# sch_claudia-2_0-the-real-thing_2026-05-1.net
KiCad netlist of a schematic drawn in EasyEDA
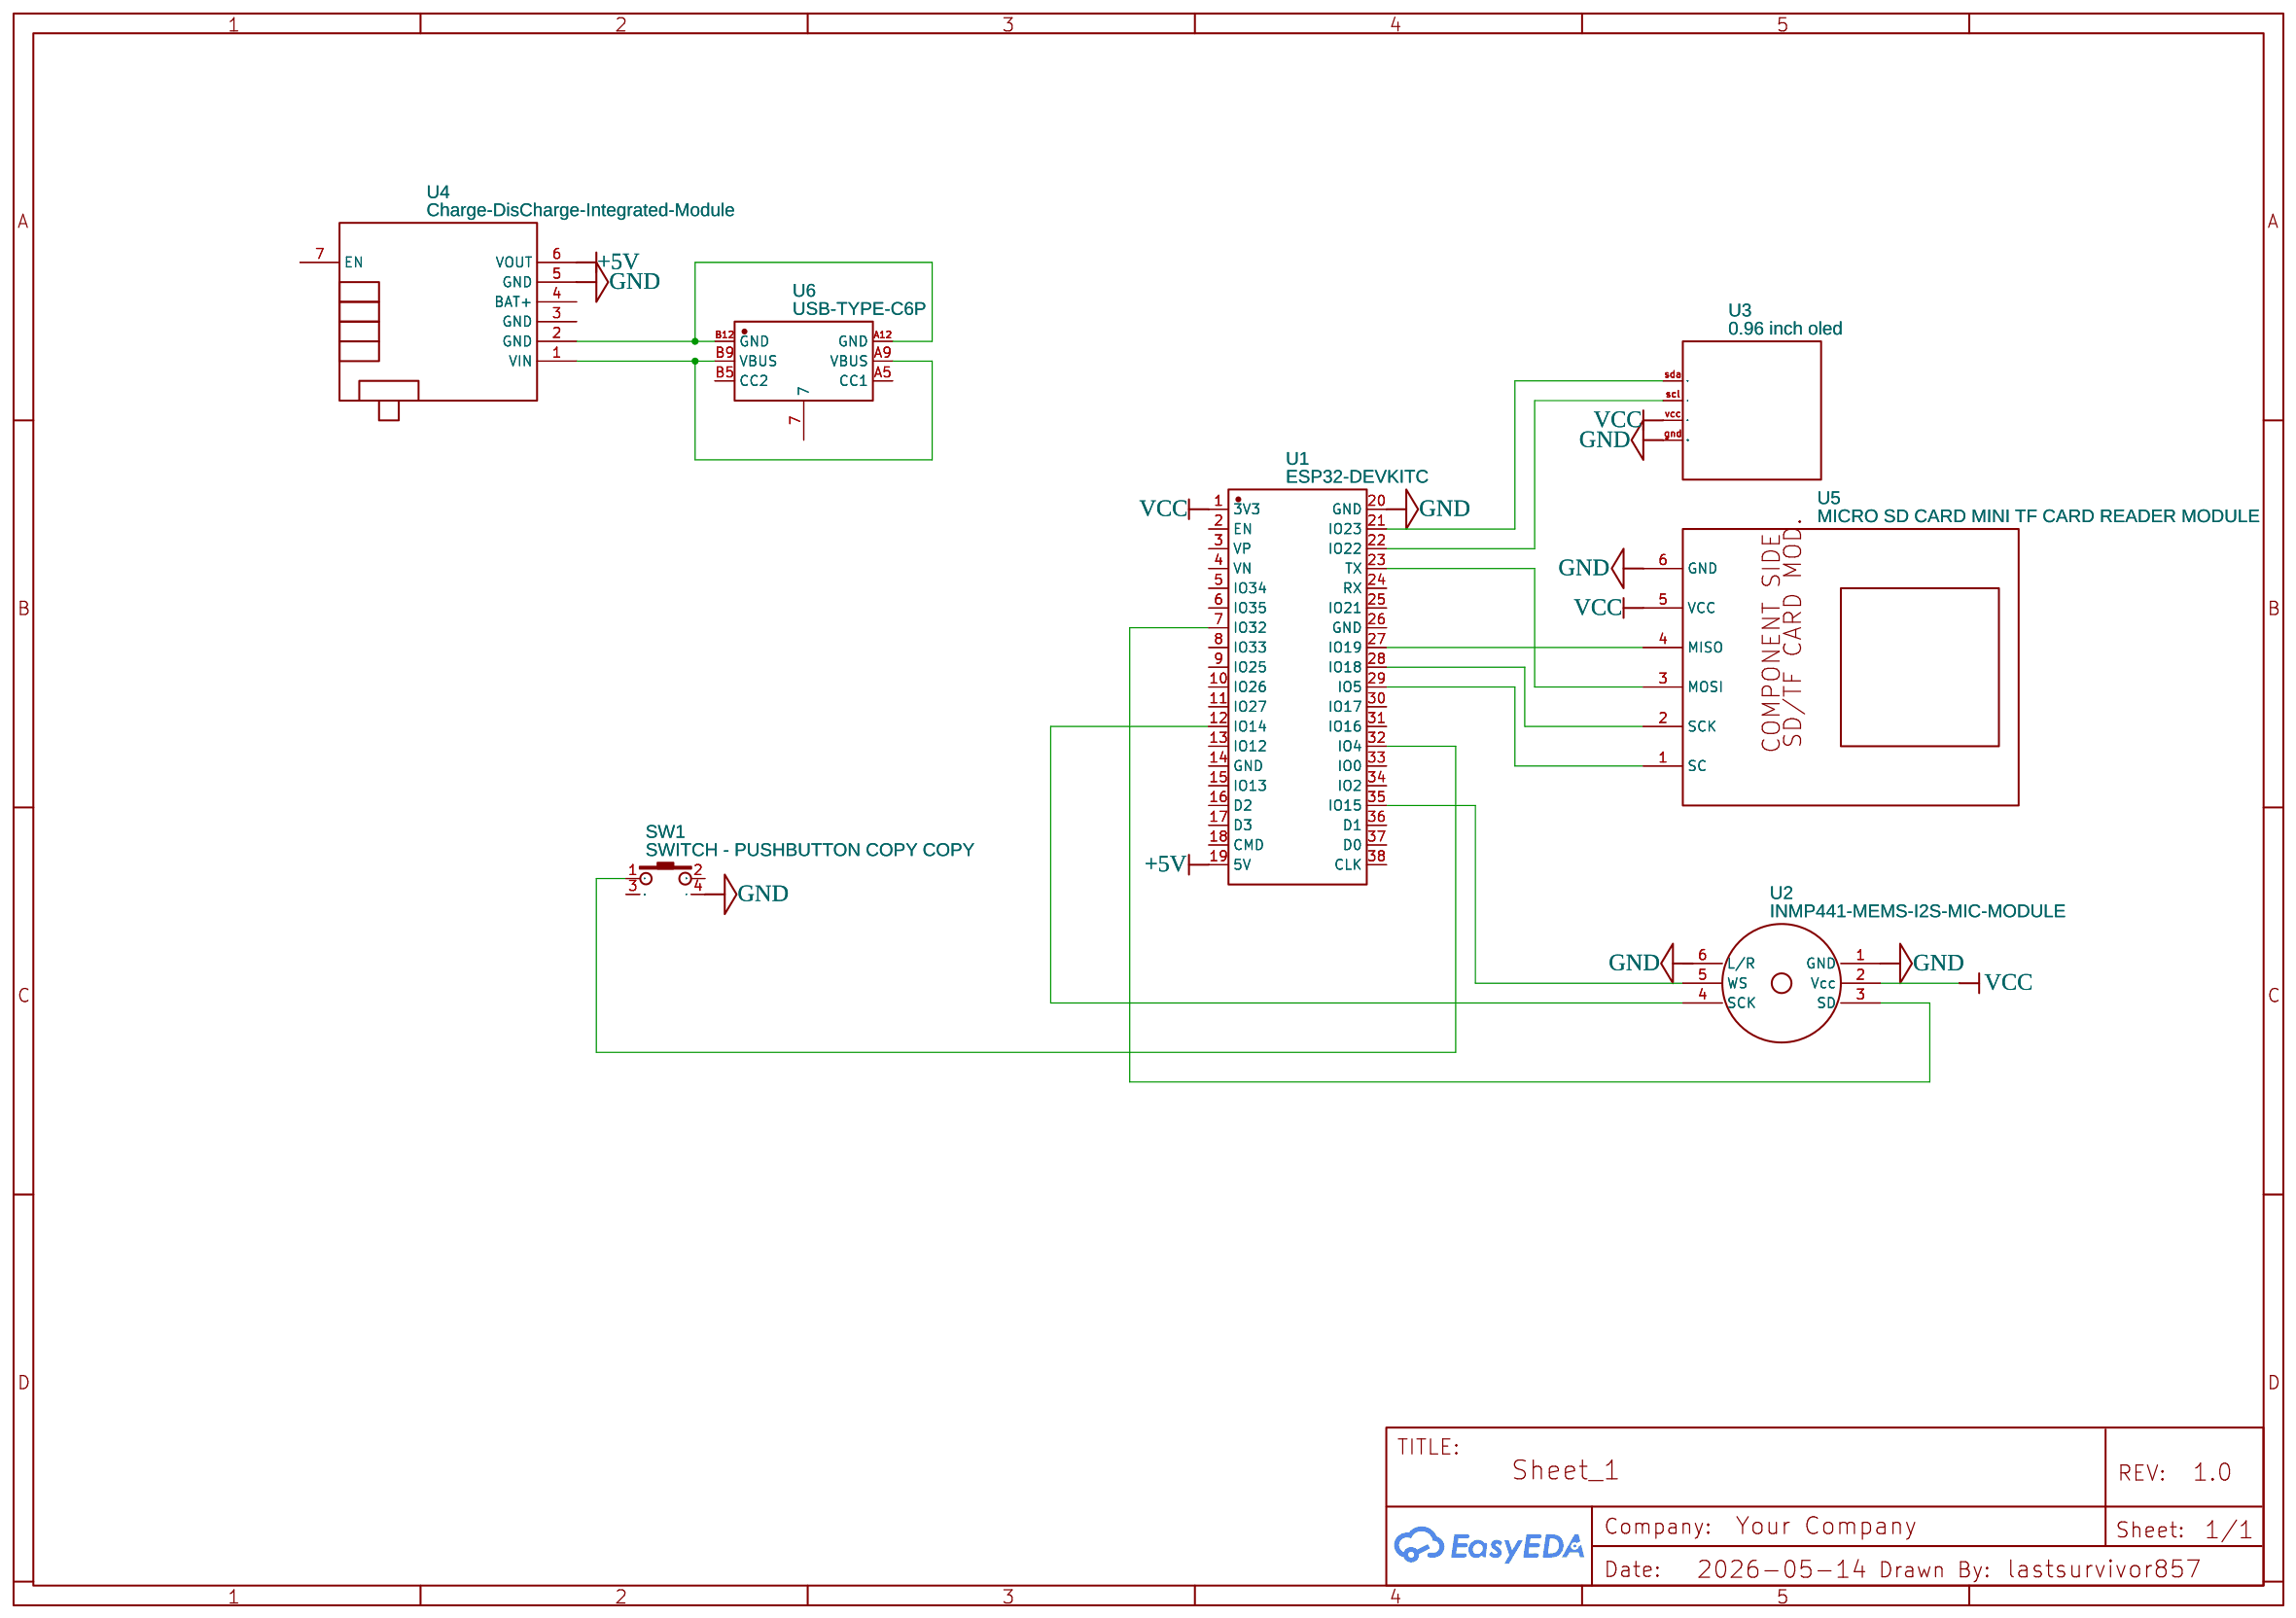
[diagram p0: schematic sheet]

(export (version "E")
  (design (tool "Eeschema 10.0.6"))
  (components
    (comp (ref "SW1") (value "SWITCH - PUSHBUTTON COPY COPY") (libsource (lib "") (part "push button reset")))
    (comp (ref "U1")
      (value "ESP32-DEVKITC")
      (fields
        (field (name "Manufacturer Part") "ESP32-DevKitC")
        (field (name "Manufacturer") "ESPRESSIF(乐鑫)")
      )
      (libsource (lib "") (part "ESP32-DEVKITC"))
    )
    (comp (ref "U2")
      (value "INMP441-MEMS-I2S-MIC-MODULE")
      (libsource (lib "") (part "INMP441-MEMS-I2S-MIC-MODULE"))
    )
    (comp (ref "U3") (value "0.96 inch oled") (libsource (lib "") (part "0.96 inch oled")))
    (comp (ref "U4")
      (value "Charge-DisCharge-Integrated-Module")
      (libsource (lib "") (part "Charge-DisCharge-Integrated-Module"))
    )
    (comp (ref "U5")
      (value "MICRO SD CARD MINI TF CARD READER MODULE")
      (libsource (lib "") (part "MICRO SD CARD MINI TF CARD READER MODULE"))
    )
    (comp (ref "U6") (value "USB-TYPE-C6P") (libsource (lib "") (part "USB-TYPE-C6P")))
  )
  (nets
    (net (code "1") (name "+5V") (class "Default")
      (node (ref "U1") (pin "19") (pinfunction "5V_19") (pintype "unspecified"))
      (node (ref "U4") (pin "6") (pinfunction "VOUT_6") (pintype "unspecified"))
    )
    (net (code "2") (name "GND") (class "Default")
      (node (ref "SW1") (pin "4") (pinfunction "4_4") (pintype "unspecified"))
      (node (ref "U1") (pin "20") (pinfunction "GND_20") (pintype "unspecified"))
      (node (ref "U2") (pin "1") (pinfunction "GND_1") (pintype "unspecified"))
      (node (ref "U3") (pin "gnd") (pinfunction "gnd_gnd") (pintype "unspecified"))
      (node (ref "U4") (pin "5") (pinfunction "GND_5") (pintype "unspecified"))
      (node (ref "U5") (pin "6") (pinfunction "GND_6") (pintype "unspecified"))
    )
    (net (code "3") (name "Net-(U1-IO4)") (class "Default")
      (node (ref "SW1") (pin "1") (pinfunction "1_1") (pintype "unspecified"))
      (node (ref "U1") (pin "32") (pinfunction "IO4_32") (pintype "unspecified"))
    )
    (net (code "4") (name "Net-(U1-IO5)") (class "Default")
      (node (ref "U1") (pin "29") (pinfunction "IO5_29") (pintype "unspecified"))
      (node (ref "U5") (pin "1") (pinfunction "SC_1") (pintype "unspecified"))
    )
    (net (code "5") (name "Net-(U1-IO14)") (class "Default")
      (node (ref "U1") (pin "12") (pinfunction "IO14_12") (pintype "unspecified"))
      (node (ref "U2") (pin "4") (pinfunction "SCK_4") (pintype "unspecified"))
    )
    (net (code "6") (name "Net-(U1-IO15)") (class "Default")
      (node (ref "U1") (pin "35") (pinfunction "IO15_35") (pintype "unspecified"))
      (node (ref "U2") (pin "5") (pinfunction "WS_5") (pintype "unspecified"))
    )
    (net (code "7") (name "Net-(U1-IO18)") (class "Default")
      (node (ref "U1") (pin "28") (pinfunction "IO18_28") (pintype "unspecified"))
      (node (ref "U5") (pin "2") (pinfunction "SCK_2") (pintype "unspecified"))
    )
    (net (code "8") (name "Net-(U1-IO19)") (class "Default")
      (node (ref "U1") (pin "27") (pinfunction "IO19_27") (pintype "unspecified"))
      (node (ref "U5") (pin "4") (pinfunction "MISO_4") (pintype "unspecified"))
    )
    (net (code "9") (name "Net-(U1-IO22)") (class "Default")
      (node (ref "U1") (pin "22") (pinfunction "IO22_22") (pintype "unspecified"))
      (node (ref "U3") (pin "scl") (pinfunction "4_scl") (pintype "unspecified"))
    )
    (net (code "10") (name "Net-(U1-IO23)") (class "Default")
      (node (ref "U1") (pin "21") (pinfunction "IO23_21") (pintype "unspecified"))
      (node (ref "U3") (pin "sda") (pinfunction "3_sda") (pintype "unspecified"))
    )
    (net (code "11") (name "Net-(U1-IO32)") (class "Default")
      (node (ref "U1") (pin "7") (pinfunction "IO32_7") (pintype "unspecified"))
      (node (ref "U2") (pin "3") (pinfunction "SD_3") (pintype "unspecified"))
    )
    (net (code "12") (name "Net-(U1-TX)") (class "Default")
      (node (ref "U1") (pin "23") (pinfunction "TX_23") (pintype "unspecified"))
      (node (ref "U5") (pin "3") (pinfunction "MOSI_3") (pintype "unspecified"))
    )
    (net (code "13") (name "Net-(U4-GND-Pad2)") (class "Default")
      (node (ref "U4") (pin "2") (pinfunction "GND_2") (pintype "unspecified"))
      (node (ref "U6") (pin "A12") (pinfunction "GND_A12") (pintype "unspecified"))
      (node (ref "U6") (pin "B12") (pinfunction "GND_B12") (pintype "unspecified"))
    )
    (net (code "14") (name "Net-(U4-VIN)") (class "Default")
      (node (ref "U4") (pin "1") (pinfunction "VIN_1") (pintype "unspecified"))
      (node (ref "U6") (pin "A9") (pinfunction "VBUS_A9") (pintype "unspecified"))
      (node (ref "U6") (pin "B9") (pinfunction "VBUS_B9") (pintype "unspecified"))
    )
    (net (code "15") (name "VCC") (class "Default")
      (node (ref "U1") (pin "1") (pinfunction "3V3_1") (pintype "unspecified"))
      (node (ref "U2") (pin "2") (pinfunction "Vcc_2") (pintype "unspecified"))
      (node (ref "U3") (pin "vcc") (pinfunction "2_vcc") (pintype "unspecified"))
      (node (ref "U5") (pin "5") (pinfunction "VCC_5") (pintype "unspecified"))
    )
    (net (code "16") (name "unconnected-(SW1-Pad2)") (class "Default")
      (node (ref "SW1") (pin "2") (pinfunction "2_2") (pintype "unspecified"))
    )
    (net (code "17") (name "unconnected-(SW1-Pad3)") (class "Default")
      (node (ref "SW1") (pin "3") (pinfunction "3_3") (pintype "unspecified"))
    )
    (net (code "18") (name "unconnected-(U1-CLK-Pad38)") (class "Default")
      (node (ref "U1") (pin "38") (pinfunction "CLK_38") (pintype "unspecified"))
    )
    (net (code "19") (name "unconnected-(U1-CMD-Pad18)") (class "Default")
      (node (ref "U1") (pin "18") (pinfunction "CMD_18") (pintype "unspecified"))
    )
    (net (code "20") (name "unconnected-(U1-D0-Pad37)") (class "Default")
      (node (ref "U1") (pin "37") (pinfunction "D0_37") (pintype "unspecified"))
    )
    (net (code "21") (name "unconnected-(U1-D1-Pad36)") (class "Default")
      (node (ref "U1") (pin "36") (pinfunction "D1_36") (pintype "unspecified"))
    )
    (net (code "22") (name "unconnected-(U1-D2-Pad16)") (class "Default")
      (node (ref "U1") (pin "16") (pinfunction "D2_16") (pintype "unspecified"))
    )
    (net (code "23") (name "unconnected-(U1-D3-Pad17)") (class "Default")
      (node (ref "U1") (pin "17") (pinfunction "D3_17") (pintype "unspecified"))
    )
    (net (code "24") (name "unconnected-(U1-EN-Pad2)") (class "Default")
      (node (ref "U1") (pin "2") (pinfunction "EN_2") (pintype "unspecified"))
    )
    (net (code "25") (name "unconnected-(U1-GND-Pad14)") (class "Default")
      (node (ref "U1") (pin "14") (pinfunction "GND_14") (pintype "unspecified"))
    )
    (net (code "26") (name "unconnected-(U1-GND-Pad26)") (class "Default")
      (node (ref "U1") (pin "26") (pinfunction "GND_26") (pintype "unspecified"))
    )
    (net (code "27") (name "unconnected-(U1-IO0-Pad33)") (class "Default")
      (node (ref "U1") (pin "33") (pinfunction "IO0_33") (pintype "unspecified"))
    )
    (net (code "28") (name "unconnected-(U1-IO2-Pad34)") (class "Default")
      (node (ref "U1") (pin "34") (pinfunction "IO2_34") (pintype "unspecified"))
    )
    (net (code "29") (name "unconnected-(U1-IO12-Pad13)") (class "Default")
      (node (ref "U1") (pin "13") (pinfunction "IO12_13") (pintype "unspecified"))
    )
    (net (code "30") (name "unconnected-(U1-IO13-Pad15)") (class "Default")
      (node (ref "U1") (pin "15") (pinfunction "IO13_15") (pintype "unspecified"))
    )
    (net (code "31") (name "unconnected-(U1-IO16-Pad31)") (class "Default")
      (node (ref "U1") (pin "31") (pinfunction "IO16_31") (pintype "unspecified"))
    )
    (net (code "32") (name "unconnected-(U1-IO17-Pad30)") (class "Default")
      (node (ref "U1") (pin "30") (pinfunction "IO17_30") (pintype "unspecified"))
    )
    (net (code "33") (name "unconnected-(U1-IO21-Pad25)") (class "Default")
      (node (ref "U1") (pin "25") (pinfunction "IO21_25") (pintype "unspecified"))
    )
    (net (code "34") (name "unconnected-(U1-IO25-Pad9)") (class "Default")
      (node (ref "U1") (pin "9") (pinfunction "IO25_9") (pintype "unspecified"))
    )
    (net (code "35") (name "unconnected-(U1-IO26-Pad10)") (class "Default")
      (node (ref "U1") (pin "10") (pinfunction "IO26_10") (pintype "unspecified"))
    )
    (net (code "36") (name "unconnected-(U1-IO27-Pad11)") (class "Default")
      (node (ref "U1") (pin "11") (pinfunction "IO27_11") (pintype "unspecified"))
    )
    (net (code "37") (name "unconnected-(U1-IO33-Pad8)") (class "Default")
      (node (ref "U1") (pin "8") (pinfunction "IO33_8") (pintype "unspecified"))
    )
    (net (code "38") (name "unconnected-(U1-IO34-Pad5)") (class "Default")
      (node (ref "U1") (pin "5") (pinfunction "IO34_5") (pintype "unspecified"))
    )
    (net (code "39") (name "unconnected-(U1-IO35-Pad6)") (class "Default")
      (node (ref "U1") (pin "6") (pinfunction "IO35_6") (pintype "unspecified"))
    )
    (net (code "40") (name "unconnected-(U1-RX-Pad24)") (class "Default")
      (node (ref "U1") (pin "24") (pinfunction "RX_24") (pintype "unspecified"))
    )
    (net (code "41") (name "unconnected-(U1-VN-Pad4)") (class "Default")
      (node (ref "U1") (pin "4") (pinfunction "VN_4") (pintype "unspecified"))
    )
    (net (code "42") (name "unconnected-(U1-VP-Pad3)") (class "Default")
      (node (ref "U1") (pin "3") (pinfunction "VP_3") (pintype "unspecified"))
    )
    (net (code "43") (name "unconnected-(U2-L{slash}R-Pad6)") (class "Default")
      (node (ref "U2") (pin "6") (pinfunction "L/R_6") (pintype "unspecified"))
    )
    (net (code "44") (name "unconnected-(U4-BAT+-Pad4)") (class "Default")
      (node (ref "U4") (pin "4") (pinfunction "BAT+_4") (pintype "unspecified"))
    )
    (net (code "45") (name "unconnected-(U4-EN-Pad7)") (class "Default")
      (node (ref "U4") (pin "7") (pinfunction "EN_7") (pintype "unspecified"))
    )
    (net (code "46") (name "unconnected-(U4-GND-Pad3)") (class "Default")
      (node (ref "U4") (pin "3") (pinfunction "GND_3") (pintype "unspecified"))
    )
    (net (code "47") (name "unconnected-(U6-CC1-PadA5)") (class "Default")
      (node (ref "U6") (pin "A5") (pinfunction "CC1_A5") (pintype "unspecified"))
    )
    (net (code "48") (name "unconnected-(U6-CC2-PadB5)") (class "Default")
      (node (ref "U6") (pin "B5") (pinfunction "CC2_B5") (pintype "unspecified"))
    )
    (net (code "49") (name "unconnected-(U6-Pad7)") (class "Default")
      (node (ref "U6") (pin "7") (pinfunction "7_7") (pintype "unspecified"))
    )
  )
)
